# MultiRotor_v0_1.net
KiCad netlist of a schematic drawn in Altium Designer
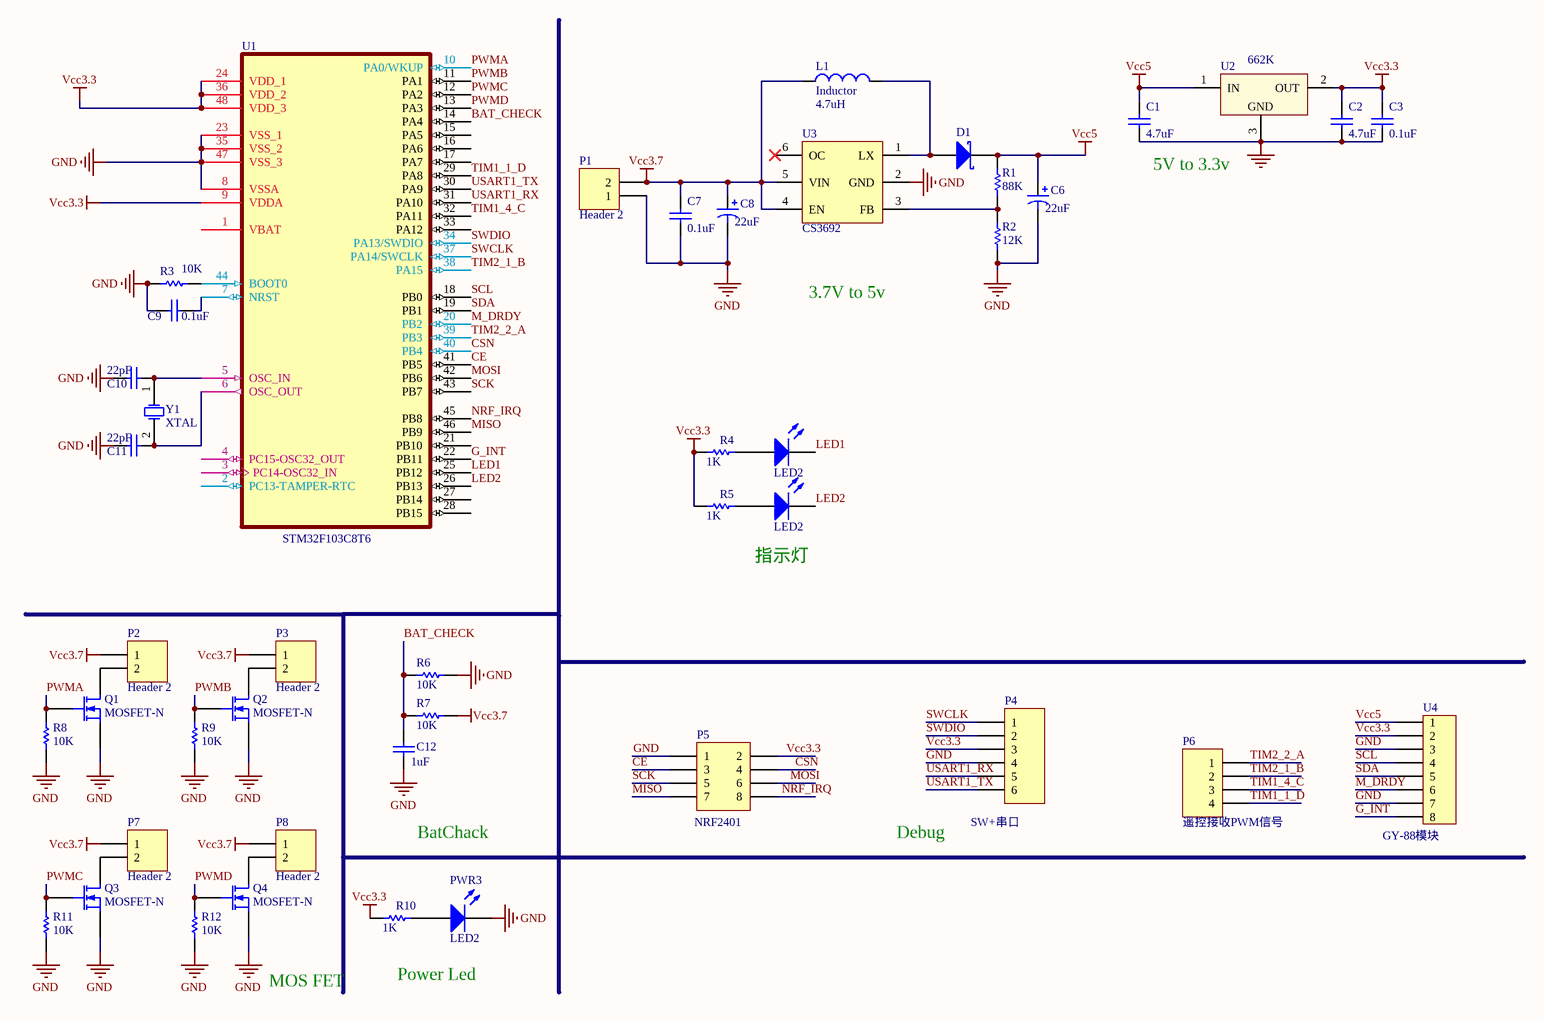
[diagram p0: MultiRotor_v0.1.SchDoc]

(export (version "E")
  (design (tool "Eeschema 10.0.6"))
  (components
    (comp (ref "C1")
      (value "4.7uF")
      (footprint "CAP[1206]")
      (description "Capacitor")
      (fields (field (name "Comment") "Cap Pol1") (field (name "PUBLISHER") "Altium Limited"))
      (libsource (lib "Miscellaneous Devices") (part "Cap"))
    )
    (comp (ref "C2")
      (value "4.7uF")
      (footprint "CAP[1206]")
      (description "Capacitor")
      (fields (field (name "Comment") "Cap Pol1") (field (name "PUBLISHER") "Altium Limited"))
      (libsource (lib "Miscellaneous Devices") (part "Cap"))
    )
    (comp (ref "C3")
      (value "0.1uF")
      (footprint "CAP[0805]")
      (description "Capacitor")
      (fields (field (name "Comment") "Cap") (field (name "PUBLISHER") "Altium Limited"))
      (libsource (lib "Miscellaneous Devices") (part "Cap"))
    )
    (comp (ref "C6")
      (value "22uF")
      (footprint "CAP[1206]")
      (description "Polarized Capacitor (Radial)")
      (fields (field (name "Comment") "Cap") (field (name "PUBLISHER") "Altium Limited"))
      (libsource (lib "Miscellaneous Devices") (part "Cap Pol1"))
    )
    (comp (ref "C7")
      (value "0.1uF")
      (footprint "CAP[0805]")
      (description "Capacitor")
      (fields (field (name "Comment") "Cap") (field (name "PUBLISHER") "Altium Limited"))
      (libsource (lib "Miscellaneous Devices") (part "Cap"))
    )
    (comp (ref "C8")
      (value "22uF")
      (footprint "CAP[1206]")
      (description "Polarized Capacitor (Radial)")
      (fields (field (name "Comment") "Cap") (field (name "PUBLISHER") "Altium Limited"))
      (libsource (lib "Miscellaneous Devices") (part "Cap Pol1"))
    )
    (comp (ref "C9")
      (value "0.1uF")
      (footprint "CAP[0805]")
      (description "Capacitor")
      (fields (field (name "Comment") "Cap") (field (name "PUBLISHER") "Altium Limited"))
      (libsource (lib "Miscellaneous Devices") (part "Cap"))
    )
    (comp (ref "C10")
      (value "22pF")
      (footprint "CAP[0805]")
      (description "Capacitor")
      (fields (field (name "Comment") "Cap") (field (name "PUBLISHER") "Altium Limited"))
      (libsource (lib "Miscellaneous Devices") (part "Cap"))
    )
    (comp (ref "C11")
      (value "22pF")
      (footprint "CAP[0805]")
      (description "Capacitor")
      (fields (field (name "Comment") "Cap") (field (name "PUBLISHER") "Altium Limited"))
      (libsource (lib "Miscellaneous Devices") (part "Cap"))
    )
    (comp (ref "C12")
      (value "1uF")
      (footprint "CAP[0805]")
      (description "Capacitor")
      (fields (field (name "Comment") "Cap") (field (name "PUBLISHER") "Altium Limited"))
      (libsource (lib "Miscellaneous Devices") (part "Cap"))
    )
    (comp (ref "D1")
      (value "1n5819")
      (footprint "DO-214AC - Diode")
      (description "Diode_P6KE")
      (libsource (lib "BY") (part "Diode_P6KE"))
    )
    (comp (ref "L1")
      (value "Inductor")
      (footprint "Inductor_T10uH")
      (fields (field (name "ALTIUM_UNNAMED_1") "4.7uH"))
      (libsource (lib "BY") (part "Inductor"))
    )
    (comp (ref "P1")
      (value "Header 2")
      (footprint "H2.54-1X2")
      (description "Header, 2-Pin")
      (fields (field (name "PUBLISHER") "Altium Limited"))
      (libsource (lib "") (part "Header 2_1"))
    )
    (comp (ref "P2")
      (value "Header 2")
      (footprint "H2.54-1X2")
      (description "Header, 2-Pin")
      (fields (field (name "PUBLISHER") "Altium Limited"))
      (libsource (lib "Miscellaneous Connectors") (part "Header 2"))
    )
    (comp (ref "P3")
      (value "Header 2")
      (footprint "H2.54-1X2")
      (description "Header, 2-Pin")
      (fields (field (name "PUBLISHER") "Altium Limited"))
      (libsource (lib "Miscellaneous Connectors") (part "Header 2"))
    )
    (comp (ref "P4")
      (value "SW+串口")
      (footprint "HDR1X6")
      (description "Header, 6-Pin")
      (fields (field (name "PUBLISHER") "Altium Limited"))
      (libsource (lib "Miscellaneous Connectors") (part "Header 6"))
    )
    (comp (ref "P5")
      (value "NRF2401")
      (footprint "NRF(2401)模块")
      (description "Header, 4-Pin, Dual row")
      (fields (field (name "PUBLISHER") "Altium Limited"))
      (libsource (lib "Miscellaneous Connectors") (part "Header 4X2"))
    )
    (comp (ref "P6")
      (value "遥控接收PWM信号")
      (footprint "H2.54-1X4")
      (description "Header, 4-Pin")
      (fields (field (name "PUBLISHER") "Altium Limited"))
      (libsource (lib "Miscellaneous Connectors") (part "Header 4"))
    )
    (comp (ref "P7")
      (value "Header 2")
      (footprint "H2.54-1X2")
      (description "Header, 2-Pin")
      (fields (field (name "PUBLISHER") "Altium Limited"))
      (libsource (lib "Miscellaneous Connectors") (part "Header 2"))
    )
    (comp (ref "P8")
      (value "Header 2")
      (footprint "H2.54-1X2")
      (description "Header, 2-Pin")
      (fields (field (name "PUBLISHER") "Altium Limited"))
      (libsource (lib "Miscellaneous Connectors") (part "Header 2"))
    )
    (comp (ref "PWR1")
      (value "LED2")
      (footprint "LED[0805]")
      (description "Typical RED, GREEN, YELLOW, AMBER GaAs LED")
      (fields (field (name "PUBLISHER") "Altium Limited"))
      (libsource (lib "Miscellaneous Devices") (part "LED2"))
    )
    (comp (ref "PWR2")
      (value "LED2")
      (footprint "LED[0805]")
      (description "Typical RED, GREEN, YELLOW, AMBER GaAs LED")
      (fields (field (name "PUBLISHER") "Altium Limited"))
      (libsource (lib "Miscellaneous Devices") (part "LED2"))
    )
    (comp (ref "PWR3")
      (value "LED2")
      (footprint "LED[0805]")
      (description "Typical RED, GREEN, YELLOW, AMBER GaAs LED")
      (fields (field (name "PUBLISHER") "Altium Limited"))
      (libsource (lib "Miscellaneous Devices") (part "LED2"))
    )
    (comp (ref "Q1")
      (value "MOSFET-N")
      (footprint "SOT23")
      (description "N-Channel MOSFET")
      (fields (field (name "PUBLISHER") "Altium Limited"))
      (libsource (lib "Miscellaneous Devices") (part "MOSFET-N"))
    )
    (comp (ref "Q2")
      (value "MOSFET-N")
      (footprint "SOT23")
      (description "N-Channel MOSFET")
      (fields (field (name "PUBLISHER") "Altium Limited"))
      (libsource (lib "Miscellaneous Devices") (part "MOSFET-N"))
    )
    (comp (ref "Q3")
      (value "MOSFET-N")
      (footprint "SOT23")
      (description "N-Channel MOSFET")
      (fields (field (name "PUBLISHER") "Altium Limited"))
      (libsource (lib "Miscellaneous Devices") (part "MOSFET-N"))
    )
    (comp (ref "Q4")
      (value "MOSFET-N")
      (footprint "SOT23")
      (description "N-Channel MOSFET")
      (fields (field (name "PUBLISHER") "Altium Limited"))
      (libsource (lib "Miscellaneous Devices") (part "MOSFET-N"))
    )
    (comp (ref "R1")
      (value "88K")
      (footprint "RES[0805]")
      (description "Resistor")
      (fields (field (name "Comment") "Res1") (field (name "PUBLISHER") "Altium Limited"))
      (libsource (lib "Miscellaneous Devices") (part "Res1"))
    )
    (comp (ref "R2")
      (value "12K")
      (footprint "RES[0805]")
      (description "Resistor")
      (fields (field (name "Comment") "Res1") (field (name "PUBLISHER") "Altium Limited"))
      (libsource (lib "Miscellaneous Devices") (part "Res1"))
    )
    (comp (ref "R3")
      (value "10K")
      (footprint "RES[0805]")
      (description "Resistor")
      (fields (field (name "Comment") "Res1") (field (name "PUBLISHER") "Altium Limited"))
      (libsource (lib "Miscellaneous Devices") (part "Res1"))
    )
    (comp (ref "R4")
      (value "1K")
      (footprint "RES[0805]")
      (description "Resistor")
      (fields (field (name "Comment") "Res1") (field (name "PUBLISHER") "Altium Limited"))
      (libsource (lib "Miscellaneous Devices") (part "Res1"))
    )
    (comp (ref "R5")
      (value "1K")
      (footprint "RES[0805]")
      (description "Resistor")
      (fields (field (name "Comment") "Res1") (field (name "PUBLISHER") "Altium Limited"))
      (libsource (lib "Miscellaneous Devices") (part "Res1"))
    )
    (comp (ref "R6")
      (value "10K")
      (footprint "RES[0805]")
      (description "Resistor")
      (fields (field (name "Comment") "Res1") (field (name "PUBLISHER") "Altium Limited"))
      (libsource (lib "Miscellaneous Devices") (part "Res1"))
    )
    (comp (ref "R7")
      (value "10K")
      (footprint "RES[0805]")
      (description "Resistor")
      (fields (field (name "Comment") "Res1") (field (name "PUBLISHER") "Altium Limited"))
      (libsource (lib "Miscellaneous Devices") (part "Res1"))
    )
    (comp (ref "R8")
      (value "10K")
      (footprint "RES[0805]")
      (description "Resistor")
      (fields (field (name "Comment") "Res1") (field (name "PUBLISHER") "Altium Limited"))
      (libsource (lib "Miscellaneous Devices") (part "Res1"))
    )
    (comp (ref "R9")
      (value "10K")
      (footprint "RES[0805]")
      (description "Resistor")
      (fields (field (name "Comment") "Res1") (field (name "PUBLISHER") "Altium Limited"))
      (libsource (lib "Miscellaneous Devices") (part "Res1"))
    )
    (comp (ref "R10")
      (value "1K")
      (footprint "RES[0805]")
      (description "Resistor")
      (fields (field (name "Comment") "Res1") (field (name "PUBLISHER") "Altium Limited"))
      (libsource (lib "Miscellaneous Devices") (part "Res1"))
    )
    (comp (ref "R11")
      (value "10K")
      (footprint "RES[0805]")
      (description "Resistor")
      (fields (field (name "Comment") "Res1") (field (name "PUBLISHER") "Altium Limited"))
      (libsource (lib "Miscellaneous Devices") (part "Res1"))
    )
    (comp (ref "R12")
      (value "10K")
      (footprint "RES[0805]")
      (description "Resistor")
      (fields (field (name "Comment") "Res1") (field (name "PUBLISHER") "Altium Limited"))
      (libsource (lib "Miscellaneous Devices") (part "Res1"))
    )
    (comp (ref "U1")
      (value "STM32F103C8T6")
      (footprint "LQFP-48")
      (description "STM32 ARM-based 32-bit MCU with 64 Kbytes Flash, 48-pin LQFP, Industrial Temperature")
      (fields (field (name "PUBLISHER") "*"))
      (libsource (lib "STM32F103C8T6") (part "STM32F103C8T6"))
    )
    (comp (ref "U2") (value "662K") (footprint "SOT23") (libsource (lib "WB") (part "AMS1117-3.3")))
    (comp (ref "U3")
      (value "CS3692")
      (footprint "SOT23-6")
      (description "Generic Phase Locked Loop")
      (fields (field (name "PUBLISHER") "Altium Limited"))
      (libsource (lib "MultiRotor") (part "CS3692"))
    )
    (comp (ref "U4") (value "GY-88模块") (footprint "MPU-6050") (libsource (lib "FAST") (part "MPU-6050模块")))
    (comp (ref "Y1")
      (value "XTAL")
      (footprint "XTAL")
      (description "Crystal Oscillator")
      (fields (field (name "PUBLISHER") "Altium Limited"))
      (libsource (lib "Miscellaneous Devices") (part "XTAL"))
    )
  )
  (nets
    (net (code "1") (name "/BAT_CHECK") (class "Default")
      (node (ref "C12") (pin "2") (pinfunction "2_2") (pintype "passive"))
      (node (ref "R6") (pin "2") (pinfunction "2_2") (pintype "passive"))
      (node (ref "R7") (pin "2") (pinfunction "2_2") (pintype "passive"))
      (node (ref "U1") (pin "14") (pinfunction "PA4_14") (pintype "bidirectional"))
    )
    (net (code "2") (name "/CE") (class "Default")
      (node (ref "P5") (pin "3") (pinfunction "3_3") (pintype "passive"))
      (node (ref "U1") (pin "41") (pinfunction "PB5_41") (pintype "bidirectional"))
    )
    (net (code "3") (name "/CSN") (class "Default")
      (node (ref "P5") (pin "4") (pinfunction "4_4") (pintype "passive"))
      (node (ref "U1") (pin "40") (pinfunction "PB4_40") (pintype "bidirectional"))
    )
    (net (code "4") (name "/G_INT") (class "Default")
      (node (ref "U1") (pin "22") (pinfunction "PB11_22") (pintype "bidirectional"))
      (node (ref "U4") (pin "8") (pinfunction "8_8") (pintype "passive"))
    )
    (net (code "5") (name "/LED1") (class "Default")
      (node (ref "PWR1") (pin "2") (pinfunction "K_2") (pintype "passive"))
      (node (ref "U1") (pin "25") (pinfunction "PB12_25") (pintype "bidirectional"))
    )
    (net (code "6") (name "/LED2") (class "Default")
      (node (ref "PWR2") (pin "2") (pinfunction "K_2") (pintype "passive"))
      (node (ref "U1") (pin "26") (pinfunction "PB13_26") (pintype "bidirectional"))
    )
    (net (code "7") (name "/MISO") (class "Default")
      (node (ref "P5") (pin "7") (pinfunction "7_7") (pintype "passive"))
      (node (ref "U1") (pin "46") (pinfunction "PB9_46") (pintype "bidirectional"))
    )
    (net (code "8") (name "/MOSI") (class "Default")
      (node (ref "P5") (pin "6") (pinfunction "6_6") (pintype "passive"))
      (node (ref "U1") (pin "42") (pinfunction "PB6_42") (pintype "bidirectional"))
    )
    (net (code "9") (name "/M_DRDY") (class "Default")
      (node (ref "U1") (pin "20") (pinfunction "PB2_20") (pintype "bidirectional"))
      (node (ref "U4") (pin "6") (pinfunction "6_6") (pintype "passive"))
    )
    (net (code "10") (name "/NRF_IRQ") (class "Default")
      (node (ref "P5") (pin "8") (pinfunction "8_8") (pintype "passive"))
      (node (ref "U1") (pin "45") (pinfunction "PB8_45") (pintype "bidirectional"))
    )
    (net (code "11") (name "/PWMA") (class "Default")
      (node (ref "Q1") (pin "2") (pinfunction "G_2") (pintype "passive"))
      (node (ref "R8") (pin "2") (pinfunction "2_2") (pintype "passive"))
      (node (ref "U1") (pin "10") (pinfunction "PA0/WKUP_10") (pintype "bidirectional"))
    )
    (net (code "12") (name "/PWMB") (class "Default")
      (node (ref "Q2") (pin "2") (pinfunction "G_2") (pintype "passive"))
      (node (ref "R9") (pin "2") (pinfunction "2_2") (pintype "passive"))
      (node (ref "U1") (pin "11") (pinfunction "PA1_11") (pintype "bidirectional"))
    )
    (net (code "13") (name "/PWMC") (class "Default")
      (node (ref "Q3") (pin "2") (pinfunction "G_2") (pintype "passive"))
      (node (ref "R11") (pin "2") (pinfunction "2_2") (pintype "passive"))
      (node (ref "U1") (pin "12") (pinfunction "PA2_12") (pintype "bidirectional"))
    )
    (net (code "14") (name "/PWMD") (class "Default")
      (node (ref "Q4") (pin "2") (pinfunction "G_2") (pintype "passive"))
      (node (ref "R12") (pin "2") (pinfunction "2_2") (pintype "passive"))
      (node (ref "U1") (pin "13") (pinfunction "PA3_13") (pintype "bidirectional"))
    )
    (net (code "15") (name "/SCK") (class "Default")
      (node (ref "P5") (pin "5") (pinfunction "5_5") (pintype "passive"))
      (node (ref "U1") (pin "43") (pinfunction "PB7_43") (pintype "bidirectional"))
    )
    (net (code "16") (name "/SCL") (class "Default")
      (node (ref "U1") (pin "18") (pinfunction "PB0_18") (pintype "bidirectional"))
      (node (ref "U4") (pin "4") (pinfunction "4_4") (pintype "passive"))
    )
    (net (code "17") (name "/SDA") (class "Default")
      (node (ref "U1") (pin "19") (pinfunction "PB1_19") (pintype "bidirectional"))
      (node (ref "U4") (pin "5") (pinfunction "5_5") (pintype "passive"))
    )
    (net (code "18") (name "/SWCLK") (class "Default")
      (node (ref "P4") (pin "1") (pinfunction "1_1") (pintype "passive"))
      (node (ref "U1") (pin "37") (pinfunction "PA14/SWCLK_37") (pintype "bidirectional"))
    )
    (net (code "19") (name "/SWDIO") (class "Default")
      (node (ref "P4") (pin "2") (pinfunction "2_2") (pintype "passive"))
      (node (ref "U1") (pin "34") (pinfunction "PA13/SWDIO_34") (pintype "bidirectional"))
    )
    (net (code "20") (name "/TIM1_1_D") (class "Default")
      (node (ref "P6") (pin "4") (pinfunction "4_4") (pintype "passive"))
      (node (ref "U1") (pin "29") (pinfunction "PA8_29") (pintype "bidirectional"))
    )
    (net (code "21") (name "/TIM1_4_C") (class "Default")
      (node (ref "P6") (pin "3") (pinfunction "3_3") (pintype "passive"))
      (node (ref "U1") (pin "32") (pinfunction "PA11_32") (pintype "bidirectional"))
    )
    (net (code "22") (name "/TIM2_1_B") (class "Default")
      (node (ref "P6") (pin "2") (pinfunction "2_2") (pintype "passive"))
      (node (ref "U1") (pin "38") (pinfunction "PA15_38") (pintype "bidirectional"))
    )
    (net (code "23") (name "/TIM2_2_A") (class "Default")
      (node (ref "P6") (pin "1") (pinfunction "1_1") (pintype "passive"))
      (node (ref "U1") (pin "39") (pinfunction "PB3_39") (pintype "bidirectional"))
    )
    (net (code "24") (name "/USART1_RX") (class "Default")
      (node (ref "P4") (pin "5") (pinfunction "5_5") (pintype "passive"))
      (node (ref "U1") (pin "31") (pinfunction "PA10_31") (pintype "bidirectional"))
    )
    (net (code "25") (name "/USART1_TX") (class "Default")
      (node (ref "P4") (pin "6") (pinfunction "6_6") (pintype "passive"))
      (node (ref "U1") (pin "30") (pinfunction "PA9_30") (pintype "bidirectional"))
    )
    (net (code "26") (name "GND") (class "Default")
      (node (ref "C1") (pin "1") (pinfunction "1_1") (pintype "passive"))
      (node (ref "C10") (pin "2") (pinfunction "2_2") (pintype "passive"))
      (node (ref "C11") (pin "2") (pinfunction "2_2") (pintype "passive"))
      (node (ref "C12") (pin "1") (pinfunction "1_1") (pintype "passive"))
      (node (ref "C2") (pin "1") (pinfunction "1_1") (pintype "passive"))
      (node (ref "C3") (pin "1") (pinfunction "1_1") (pintype "passive"))
      (node (ref "C6") (pin "2") (pinfunction "2_2") (pintype "passive"))
      (node (ref "C7") (pin "1") (pinfunction "1_1") (pintype "passive"))
      (node (ref "C8") (pin "2") (pinfunction "2_2") (pintype "passive"))
      (node (ref "C9") (pin "2") (pinfunction "2_2") (pintype "passive"))
      (node (ref "P1") (pin "1") (pinfunction "1_1") (pintype "passive"))
      (node (ref "P4") (pin "4") (pinfunction "4_4") (pintype "passive"))
      (node (ref "P5") (pin "1") (pinfunction "1_1") (pintype "passive"))
      (node (ref "PWR3") (pin "2") (pinfunction "K_2") (pintype "passive"))
      (node (ref "Q1") (pin "3") (pinfunction "S_3") (pintype "passive"))
      (node (ref "Q2") (pin "3") (pinfunction "S_3") (pintype "passive"))
      (node (ref "Q3") (pin "3") (pinfunction "S_3") (pintype "passive"))
      (node (ref "Q4") (pin "3") (pinfunction "S_3") (pintype "passive"))
      (node (ref "R11") (pin "1") (pinfunction "1_1") (pintype "passive"))
      (node (ref "R12") (pin "1") (pinfunction "1_1") (pintype "passive"))
      (node (ref "R2") (pin "2") (pinfunction "2_2") (pintype "passive"))
      (node (ref "R3") (pin "2") (pinfunction "2_2") (pintype "passive"))
      (node (ref "R6") (pin "1") (pinfunction "1_1") (pintype "passive"))
      (node (ref "R8") (pin "1") (pinfunction "1_1") (pintype "passive"))
      (node (ref "R9") (pin "1") (pinfunction "1_1") (pintype "passive"))
      (node (ref "U1") (pin "23") (pinfunction "VSS_1_23") (pintype "power_in"))
      (node (ref "U1") (pin "35") (pinfunction "VSS_2_35") (pintype "power_in"))
      (node (ref "U1") (pin "47") (pinfunction "VSS_3_47") (pintype "power_in"))
      (node (ref "U1") (pin "8") (pinfunction "VSSA_8") (pintype "power_in"))
      (node (ref "U2") (pin "3") (pinfunction "GND_3") (pintype "passive"))
      (node (ref "U3") (pin "2") (pinfunction "GND_2") (pintype "passive"))
      (node (ref "U4") (pin "3") (pinfunction "3_3") (pintype "passive"))
      (node (ref "U4") (pin "7") (pinfunction "7_7") (pintype "passive"))
    )
    (net (code "27") (name "Net-(D1-A)") (class "Default")
      (node (ref "D1") (pin "1") (pinfunction "A_1") (pintype "passive"))
      (node (ref "L1") (pin "2") (pinfunction "2_2") (pintype "passive"))
      (node (ref "U3") (pin "1") (pinfunction "LX_1") (pintype "passive"))
    )
    (net (code "28") (name "Net-(PWR1-A)") (class "Default")
      (node (ref "PWR1") (pin "1") (pinfunction "A_1") (pintype "passive"))
      (node (ref "R4") (pin "1") (pinfunction "1_1") (pintype "passive"))
    )
    (net (code "29") (name "Net-(PWR2-A)") (class "Default")
      (node (ref "PWR2") (pin "1") (pinfunction "A_1") (pintype "passive"))
      (node (ref "R5") (pin "1") (pinfunction "1_1") (pintype "passive"))
    )
    (net (code "30") (name "Net-(PWR3-A)") (class "Default")
      (node (ref "PWR3") (pin "1") (pinfunction "A_1") (pintype "passive"))
      (node (ref "R10") (pin "1") (pinfunction "1_1") (pintype "passive"))
    )
    (net (code "31") (name "Net-(Q1-D)") (class "Default")
      (node (ref "P2") (pin "2") (pinfunction "2_2") (pintype "passive"))
      (node (ref "Q1") (pin "1") (pinfunction "D_1") (pintype "passive"))
    )
    (net (code "32") (name "Net-(Q2-D)") (class "Default")
      (node (ref "P3") (pin "2") (pinfunction "2_2") (pintype "passive"))
      (node (ref "Q2") (pin "1") (pinfunction "D_1") (pintype "passive"))
    )
    (net (code "33") (name "Net-(Q3-D)") (class "Default")
      (node (ref "P7") (pin "2") (pinfunction "2_2") (pintype "passive"))
      (node (ref "Q3") (pin "1") (pinfunction "D_1") (pintype "passive"))
    )
    (net (code "34") (name "Net-(Q4-D)") (class "Default")
      (node (ref "P8") (pin "2") (pinfunction "2_2") (pintype "passive"))
      (node (ref "Q4") (pin "1") (pinfunction "D_1") (pintype "passive"))
    )
    (net (code "35") (name "Net-(U1-BOOT0)") (class "Default")
      (node (ref "R3") (pin "1") (pinfunction "1_1") (pintype "passive"))
      (node (ref "U1") (pin "44") (pinfunction "BOOT0_44") (pintype "input"))
    )
    (net (code "36") (name "Net-(U1-NRST)") (class "Default")
      (node (ref "C9") (pin "1") (pinfunction "1_1") (pintype "passive"))
      (node (ref "U1") (pin "7") (pinfunction "NRST_7") (pintype "bidirectional"))
    )
    (net (code "37") (name "Net-(U1-OSC_IN)") (class "Default")
      (node (ref "C10") (pin "1") (pinfunction "1_1") (pintype "passive"))
      (node (ref "U1") (pin "5") (pinfunction "OSC_IN_5") (pintype "input"))
      (node (ref "Y1") (pin "1") (pinfunction "OSC1_1") (pintype "passive"))
    )
    (net (code "38") (name "Net-(U1-OSC_OUT)") (class "Default")
      (node (ref "C11") (pin "1") (pinfunction "1_1") (pintype "passive"))
      (node (ref "U1") (pin "6") (pinfunction "OSC_OUT_6") (pintype "output"))
      (node (ref "Y1") (pin "2") (pinfunction "OSC2_2") (pintype "passive"))
    )
    (net (code "39") (name "Net-(U3-FB)") (class "Default")
      (node (ref "R1") (pin "2") (pinfunction "2_2") (pintype "passive"))
      (node (ref "R2") (pin "1") (pinfunction "1_1") (pintype "passive"))
      (node (ref "U3") (pin "3") (pinfunction "FB_3") (pintype "passive"))
    )
    (net (code "40") (name "Vcc3.3") (class "Default")
      (node (ref "C2") (pin "2") (pinfunction "2_2") (pintype "passive"))
      (node (ref "C3") (pin "2") (pinfunction "2_2") (pintype "passive"))
      (node (ref "P4") (pin "3") (pinfunction "3_3") (pintype "passive"))
      (node (ref "P5") (pin "2") (pinfunction "2_2") (pintype "passive"))
      (node (ref "R10") (pin "2") (pinfunction "2_2") (pintype "passive"))
      (node (ref "R4") (pin "2") (pinfunction "2_2") (pintype "passive"))
      (node (ref "R5") (pin "2") (pinfunction "2_2") (pintype "passive"))
      (node (ref "U1") (pin "24") (pinfunction "VDD_1_24") (pintype "power_in"))
      (node (ref "U1") (pin "36") (pinfunction "VDD_2_36") (pintype "power_in"))
      (node (ref "U1") (pin "48") (pinfunction "VDD_3_48") (pintype "power_in"))
      (node (ref "U1") (pin "9") (pinfunction "VDDA_9") (pintype "power_in"))
      (node (ref "U2") (pin "2") (pinfunction "OUT_2") (pintype "passive"))
      (node (ref "U4") (pin "2") (pinfunction "2_2") (pintype "passive"))
    )
    (net (code "41") (name "Vcc3.7") (class "Default")
      (node (ref "C7") (pin "2") (pinfunction "2_2") (pintype "passive"))
      (node (ref "C8") (pin "1") (pinfunction "1_1") (pintype "passive"))
      (node (ref "L1") (pin "1") (pinfunction "1_1") (pintype "passive"))
      (node (ref "P1") (pin "2") (pinfunction "2_2") (pintype "passive"))
      (node (ref "P2") (pin "1") (pinfunction "1_1") (pintype "passive"))
      (node (ref "P3") (pin "1") (pinfunction "1_1") (pintype "passive"))
      (node (ref "P7") (pin "1") (pinfunction "1_1") (pintype "passive"))
      (node (ref "P8") (pin "1") (pinfunction "1_1") (pintype "passive"))
      (node (ref "R7") (pin "1") (pinfunction "1_1") (pintype "passive"))
      (node (ref "U3") (pin "4") (pinfunction "EN_4") (pintype "passive"))
      (node (ref "U3") (pin "5") (pinfunction "VIN_5") (pintype "passive"))
    )
    (net (code "42") (name "Vcc5") (class "Default")
      (node (ref "C1") (pin "2") (pinfunction "2_2") (pintype "passive"))
      (node (ref "C6") (pin "1") (pinfunction "1_1") (pintype "passive"))
      (node (ref "D1") (pin "2") (pinfunction "K_2") (pintype "passive"))
      (node (ref "R1") (pin "1") (pinfunction "1_1") (pintype "passive"))
      (node (ref "U2") (pin "1") (pinfunction "IN_1") (pintype "passive"))
      (node (ref "U4") (pin "1") (pinfunction "1_1") (pintype "passive"))
    )
    (net (code "43") (name "unconnected-(U1-PA5-Pad15)") (class "Default")
      (node (ref "U1") (pin "15") (pinfunction "PA5_15") (pintype "bidirectional"))
    )
    (net (code "44") (name "unconnected-(U1-PA6-Pad16)") (class "Default")
      (node (ref "U1") (pin "16") (pinfunction "PA6_16") (pintype "bidirectional"))
    )
    (net (code "45") (name "unconnected-(U1-PA7-Pad17)") (class "Default")
      (node (ref "U1") (pin "17") (pinfunction "PA7_17") (pintype "bidirectional"))
    )
    (net (code "46") (name "unconnected-(U1-PA12-Pad33)") (class "Default")
      (node (ref "U1") (pin "33") (pinfunction "PA12_33") (pintype "bidirectional"))
    )
    (net (code "47") (name "unconnected-(U1-PB10-Pad21)") (class "Default")
      (node (ref "U1") (pin "21") (pinfunction "PB10_21") (pintype "bidirectional"))
    )
    (net (code "48") (name "unconnected-(U1-PB14-Pad27)") (class "Default")
      (node (ref "U1") (pin "27") (pinfunction "PB14_27") (pintype "bidirectional"))
    )
    (net (code "49") (name "unconnected-(U1-PB15-Pad28)") (class "Default")
      (node (ref "U1") (pin "28") (pinfunction "PB15_28") (pintype "bidirectional"))
    )
    (net (code "50") (name "unconnected-(U1-PC13-TAMPER-RTC-Pad2)") (class "Default")
      (node (ref "U1") (pin "2") (pinfunction "PC13-TAMPER-RTC_2") (pintype "bidirectional"))
    )
    (net (code "51") (name "unconnected-(U1-PC14-OSC32_IN-Pad3)") (class "Default")
      (node (ref "U1") (pin "3") (pinfunction "PC14-OSC32_IN_3") (pintype "bidirectional"))
    )
    (net (code "52") (name "unconnected-(U1-PC15-OSC32_OUT-Pad4)") (class "Default")
      (node (ref "U1") (pin "4") (pinfunction "PC15-OSC32_OUT_4") (pintype "bidirectional"))
    )
    (net (code "53") (name "unconnected-(U1-VBAT-Pad1)") (class "Default")
      (node (ref "U1") (pin "1") (pinfunction "VBAT_1") (pintype "power_in"))
    )
    (net (code "54") (name "unconnected-(U3-OC-Pad6)") (class "Default")
      (node (ref "U3") (pin "6") (pinfunction "OC_6") (pintype "passive+no_connect"))
    )
  )
)
